# contact-block-v4.net
KiCad netlist of a schematic drawn in EAGLE
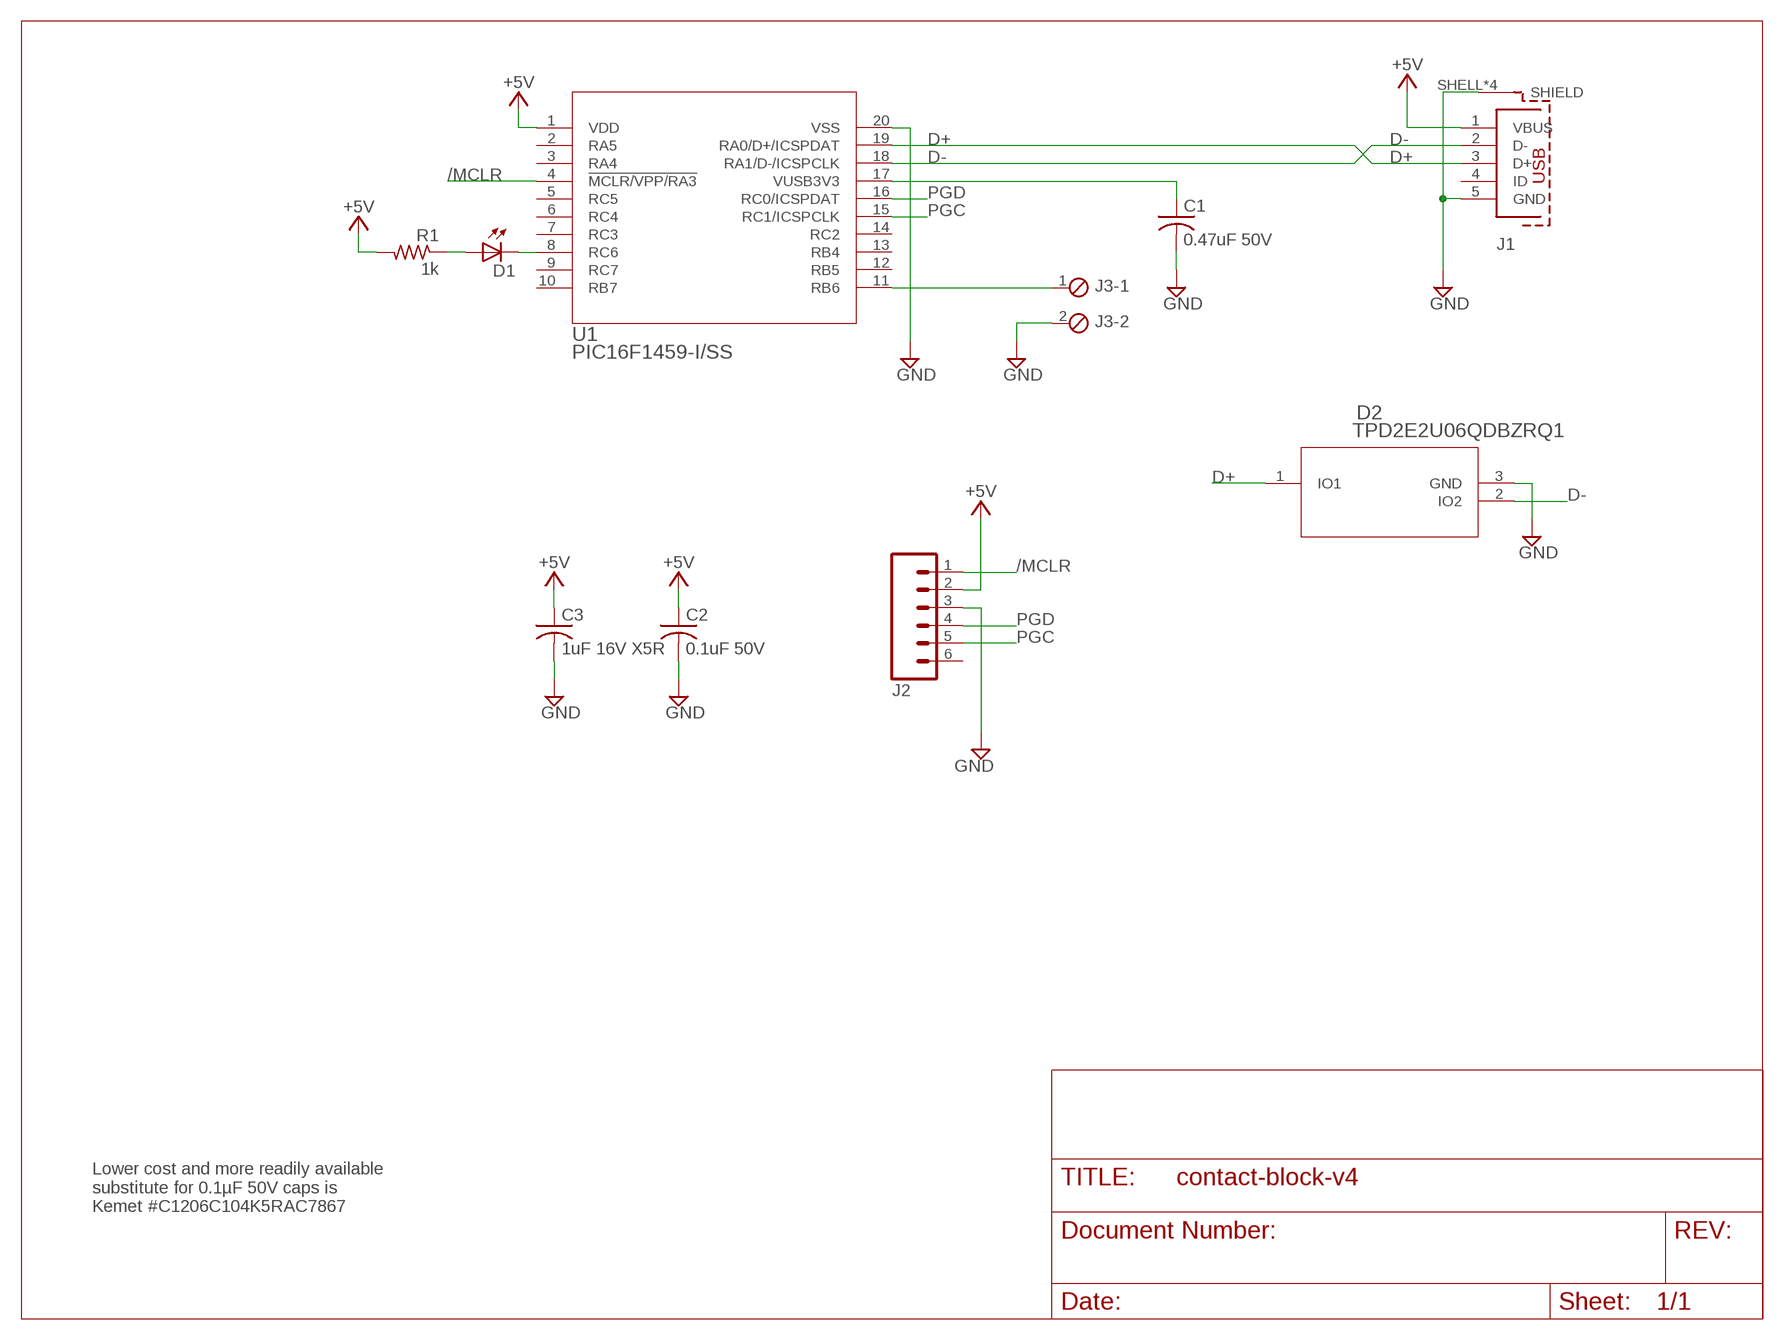
[diagram p0: schematic, sheet 1]

(export (version "E")
  (design (tool "Eeschema 10.0.6"))
  (components
    (comp (ref "C1")
      (value "0.47uF 50V")
      (footprint "eagle-import:C1206K")
      (fields (field (name "MFR") "KEMET") (field (name "MFR_PART_NO") "C1206C474K5RACTU"))
      (libsource (lib "eagle-import") (part "C-USC1206K"))
    )
    (comp (ref "C2")
      (value "0.1uF 50V")
      (footprint "eagle-import:C1206K")
      (fields (field (name "MFR") "KEMET") (field (name "MFR_PART_NO") "C1206S104M5RACTU"))
      (libsource (lib "eagle-import") (part "C-USC1206K"))
    )
    (comp (ref "C3")
      (value "1uF 16V X5R")
      (footprint "eagle-import:C1210")
      (fields (field (name "MFR") "KEMET") (field (name "MFR_PART_NO") "C1210C105K4PACTU"))
      (libsource (lib "eagle-import") (part "C-USC1210"))
    )
    (comp (ref "D1")
      (value "LEDKA-3528ASYC")
      (footprint "eagle-import:KA-3528ASYC")
      (libsource (lib "eagle-import") (part "LEDKA-3528ASYC"))
    )
    (comp (ref "D2")
      (value "TPD2E2U06QDBZRQ1")
      (footprint "eagle-import:DBZ3")
      (libsource (lib "eagle-import") (part "TPD2E2U06QDBZRQ1"))
    )
    (comp (ref "J1")
      (value "629105136821")
      (footprint "eagle-import:629105136821")
      (libsource (lib "eagle-import") (part "629105136821"))
    )
    (comp (ref "J2")
      (value "M06SIP")
      (footprint "eagle-import:1X06")
      (libsource (lib "eagle-import") (part "M06SIP"))
    )
    (comp (ref "J3")
      (value "MPT2")
      (footprint "eagle-import:2POL254")
      (libsource (lib "eagle-import") (part "MPT2"))
    )
    (comp (ref "R1")
      (value "1k")
      (footprint "eagle-import:R1206")
      (fields (field (name "MFR") "BOURNS") (field (name "MFR_PART_NO") "CR1206-JW-102ELF"))
      (libsource (lib "eagle-import") (part "R-US_R1206"))
    )
    (comp (ref "U1")
      (value "PIC16F1459-I/SS")
      (footprint "eagle-import:SSOP20_MC")
      (fields (field (name "MANUFACTURER_PART_NUMBER") "PIC16F1459ISS"))
      (libsource (lib "eagle-import") (part "PIC16F1459-I/SS"))
    )
  )
  (nets
    (net (code "1") (name "+5V") (class "Default")
      (node (ref "C2") (pin "1") (pinfunction "1_1") (pintype "passive"))
      (node (ref "C3") (pin "1") (pinfunction "1_1") (pintype "passive"))
      (node (ref "J1") (pin "1") (pinfunction "VBUS_1") (pintype "passive"))
      (node (ref "J2") (pin "2") (pinfunction "2_2") (pintype "passive"))
      (node (ref "R1") (pin "2") (pinfunction "2_2") (pintype "passive"))
      (node (ref "U1") (pin "1") (pinfunction "VDD_1") (pintype "power_in"))
    )
    (net (code "2") (name "/D+") (class "Default")
      (node (ref "D2") (pin "1") (pinfunction "IO1_1") (pintype "bidirectional"))
      (node (ref "J1") (pin "3") (pinfunction "D+_3") (pintype "passive"))
      (node (ref "U1") (pin "19") (pinfunction "RA0/D+/ICSPDAT_19") (pintype "bidirectional"))
    )
    (net (code "3") (name "/D-") (class "Default")
      (node (ref "D2") (pin "2") (pinfunction "IO2_2") (pintype "bidirectional"))
      (node (ref "J1") (pin "2") (pinfunction "D-_2") (pintype "passive"))
      (node (ref "U1") (pin "18") (pinfunction "RA1/D-/ICSPCLK_18") (pintype "bidirectional"))
    )
    (net (code "4") (name "/PGC") (class "Default")
      (node (ref "J2") (pin "5") (pinfunction "5_5") (pintype "passive"))
      (node (ref "U1") (pin "15") (pinfunction "RC1/ICSPCLK_15") (pintype "bidirectional"))
    )
    (net (code "5") (name "/PGD") (class "Default")
      (node (ref "J2") (pin "4") (pinfunction "4_4") (pintype "passive"))
      (node (ref "U1") (pin "16") (pinfunction "RC0/ICSPDAT_16") (pintype "bidirectional"))
    )
    (net (code "6") (name "/{slash}MCLR") (class "Default")
      (node (ref "J2") (pin "1") (pinfunction "1_1") (pintype "passive"))
      (node (ref "U1") (pin "4") (pinfunction "~{MCLR/VPP/RA3}_4") (pintype "bidirectional"))
    )
    (net (code "7") (name "GND") (class "Default")
      (node (ref "C1") (pin "2") (pinfunction "2_2") (pintype "passive"))
      (node (ref "C2") (pin "2") (pinfunction "2_2") (pintype "passive"))
      (node (ref "C3") (pin "2") (pinfunction "2_2") (pintype "passive"))
      (node (ref "D2") (pin "3") (pinfunction "GND_3") (pintype "power_in"))
      (node (ref "J1") (pin "5") (pinfunction "GND_5") (pintype "passive"))
      (node (ref "J1") (pin "SHELL") (pinfunction "SHIELD_SHELL") (pintype "passive"))
      (node (ref "J1") (pin "SHELL1") (pinfunction "SHIELD_SHELL1") (pintype "passive"))
      (node (ref "J1") (pin "SHELL2") (pinfunction "SHIELD_SHELL2") (pintype "passive"))
      (node (ref "J1") (pin "SHELL3") (pinfunction "SHIELD_SHELL3") (pintype "passive"))
      (node (ref "J2") (pin "3") (pinfunction "3_3") (pintype "passive"))
      (node (ref "J3") (pin "2") (pinfunction "1_2") (pintype "passive"))
      (node (ref "U1") (pin "20") (pinfunction "VSS_20") (pintype "power_in"))
    )
    (net (code "8") (name "Net-(D1-PadA)") (class "Default")
      (node (ref "D1") (pin "A") (pinfunction "A_A") (pintype "passive"))
      (node (ref "R1") (pin "1") (pinfunction "1_1") (pintype "passive"))
    )
    (net (code "9") (name "Net-(U1-RB6)") (class "Default")
      (node (ref "J3") (pin "1") (pinfunction "1_1") (pintype "passive"))
      (node (ref "U1") (pin "11") (pinfunction "RB6_11") (pintype "bidirectional"))
    )
    (net (code "10") (name "Net-(U1-RC6)") (class "Default")
      (node (ref "D1") (pin "C") (pinfunction "C_C") (pintype "passive"))
      (node (ref "U1") (pin "8") (pinfunction "RC6_8") (pintype "bidirectional"))
    )
    (net (code "11") (name "Net-(U1-VUSB3V3)") (class "Default")
      (node (ref "C1") (pin "1") (pinfunction "1_1") (pintype "passive"))
      (node (ref "U1") (pin "17") (pinfunction "VUSB3V3_17") (pintype "power_in"))
    )
    (net (code "12") (name "unconnected-(J1-ID-Pad4)") (class "Default")
      (node (ref "J1") (pin "4") (pinfunction "ID_4") (pintype "passive"))
    )
    (net (code "13") (name "unconnected-(J2-Pad6)") (class "Default")
      (node (ref "J2") (pin "6") (pinfunction "6_6") (pintype "passive"))
    )
    (net (code "14") (name "unconnected-(U1-RA4-Pad3)") (class "Default")
      (node (ref "U1") (pin "3") (pinfunction "RA4_3") (pintype "bidirectional"))
    )
    (net (code "15") (name "unconnected-(U1-RA5-Pad2)") (class "Default")
      (node (ref "U1") (pin "2") (pinfunction "RA5_2") (pintype "bidirectional"))
    )
    (net (code "16") (name "unconnected-(U1-RB4-Pad13)") (class "Default")
      (node (ref "U1") (pin "13") (pinfunction "RB4_13") (pintype "bidirectional"))
    )
    (net (code "17") (name "unconnected-(U1-RB5-Pad12)") (class "Default")
      (node (ref "U1") (pin "12") (pinfunction "RB5_12") (pintype "bidirectional"))
    )
    (net (code "18") (name "unconnected-(U1-RB7-Pad10)") (class "Default")
      (node (ref "U1") (pin "10") (pinfunction "RB7_10") (pintype "bidirectional"))
    )
    (net (code "19") (name "unconnected-(U1-RC2-Pad14)") (class "Default")
      (node (ref "U1") (pin "14") (pinfunction "RC2_14") (pintype "bidirectional"))
    )
    (net (code "20") (name "unconnected-(U1-RC3-Pad7)") (class "Default")
      (node (ref "U1") (pin "7") (pinfunction "RC3_7") (pintype "bidirectional"))
    )
    (net (code "21") (name "unconnected-(U1-RC4-Pad6)") (class "Default")
      (node (ref "U1") (pin "6") (pinfunction "RC4_6") (pintype "bidirectional"))
    )
    (net (code "22") (name "unconnected-(U1-RC5-Pad5)") (class "Default")
      (node (ref "U1") (pin "5") (pinfunction "RC5_5") (pintype "bidirectional"))
    )
    (net (code "23") (name "unconnected-(U1-RC7-Pad9)") (class "Default")
      (node (ref "U1") (pin "9") (pinfunction "RC7_9") (pintype "bidirectional"))
    )
  )
)
